# FM_SCH.net
KiCad netlist of a schematic drawn in Altium Designer
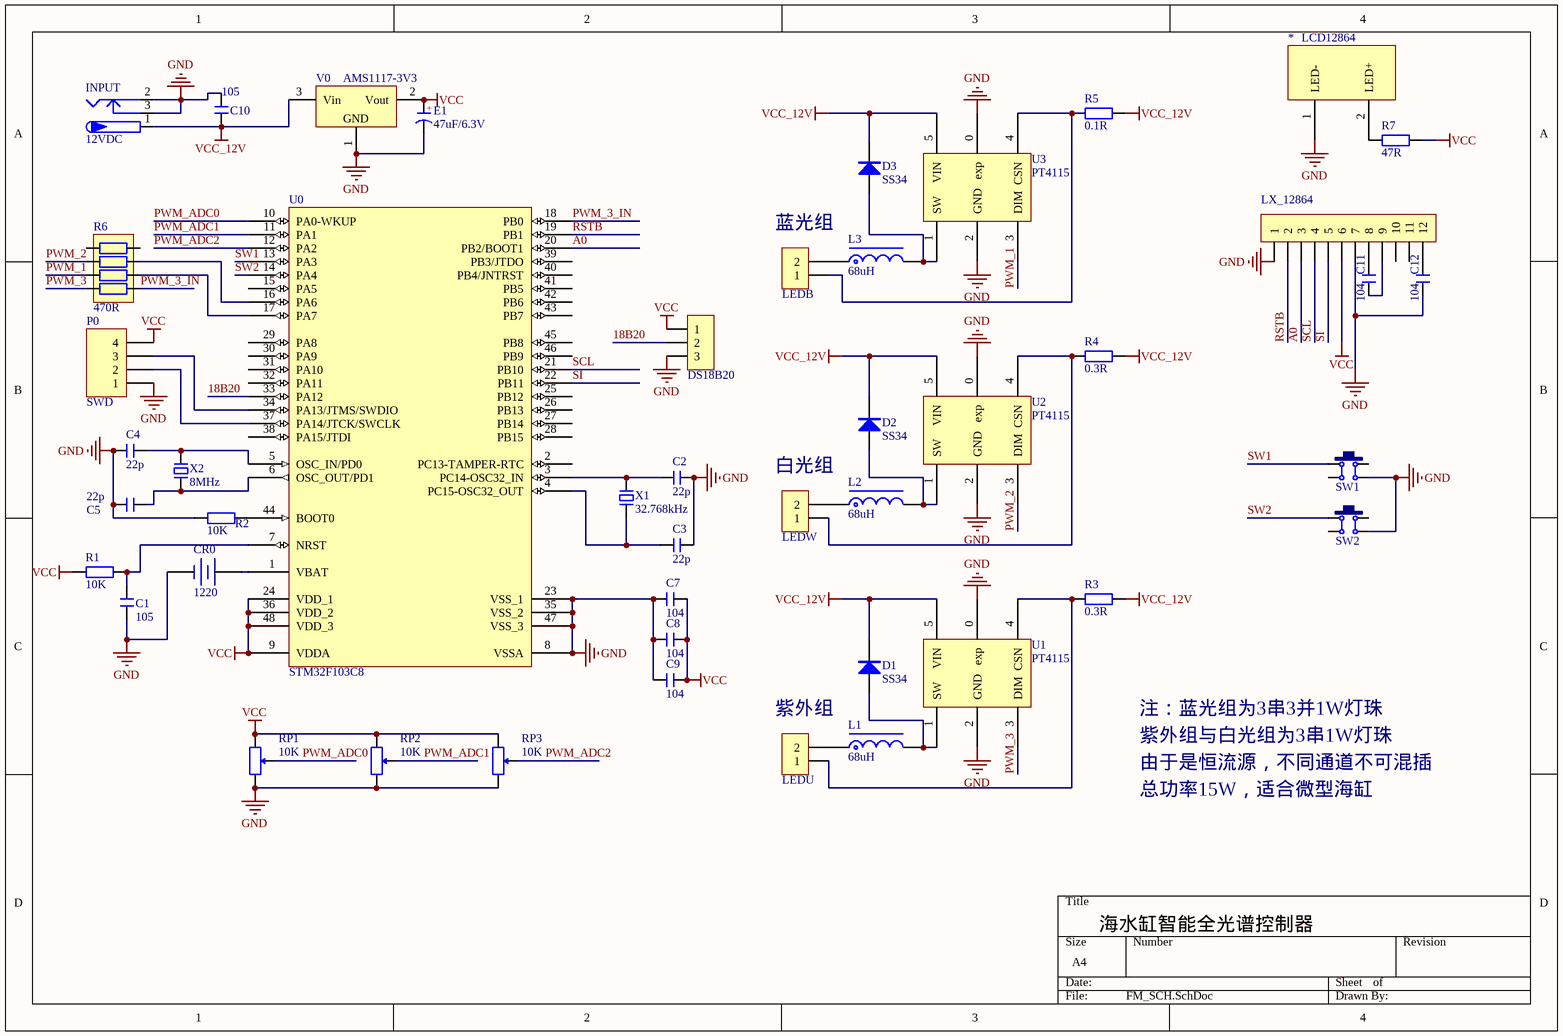
[diagram p0: FM_SCH.SchDoc]

(export (version "E")
  (design (tool "Eeschema 10.0.6"))
  (components
    (comp (ref "*") (value "LCD12864") (footprint "LX_12864") (libsource (lib "F_M_lib") (part "LCD12864")))
    (comp (ref "C1")
      (value "105")
      (footprint "C 0603_L")
      (description "无极性贴片电容")
      (fields (field (name "版权归属") "源创客"))
      (libsource (lib "3.1   - 电阻-电容-电感") (part "C"))
    )
    (comp (ref "C2")
      (value "22p")
      (footprint "C 0603_L")
      (description "无极性贴片电容")
      (fields (field (name "版权归属") "源创客"))
      (libsource (lib "3.1   - 电阻-电容-电感") (part "C"))
    )
    (comp (ref "C3")
      (value "22p")
      (footprint "C 0603_L")
      (description "无极性贴片电容")
      (fields (field (name "版权归属") "源创客"))
      (libsource (lib "3.1   - 电阻-电容-电感") (part "C"))
    )
    (comp (ref "C4")
      (value "22p")
      (footprint "C 0603_L")
      (description "无极性贴片电容")
      (fields (field (name "版权归属") "源创客"))
      (libsource (lib "3.1   - 电阻-电容-电感") (part "C"))
    )
    (comp (ref "C5")
      (value "22p")
      (footprint "C 0603_L")
      (description "无极性贴片电容")
      (fields (field (name "版权归属") "源创客"))
      (libsource (lib "3.1   - 电阻-电容-电感") (part "C"))
    )
    (comp (ref "C7")
      (value "104")
      (footprint "C 0603_L")
      (description "无极性贴片电容")
      (fields (field (name "版权归属") "源创客"))
      (libsource (lib "3.1   - 电阻-电容-电感") (part "C"))
    )
    (comp (ref "C8")
      (value "104")
      (footprint "C 0603_L")
      (description "无极性贴片电容")
      (fields (field (name "版权归属") "源创客"))
      (libsource (lib "3.1   - 电阻-电容-电感") (part "C"))
    )
    (comp (ref "C9")
      (value "104")
      (footprint "C 0603_L")
      (description "无极性贴片电容")
      (fields (field (name "版权归属") "源创客"))
      (libsource (lib "3.1   - 电阻-电容-电感") (part "C"))
    )
    (comp (ref "C10")
      (value "105")
      (footprint "C 0603_L")
      (description "无极性贴片电容")
      (fields (field (name "版权归属") "源创客"))
      (libsource (lib "3.1   - 电阻-电容-电感") (part "C"))
    )
    (comp (ref "C11")
      (value "104")
      (footprint "C 0603_L")
      (description "无极性贴片电容")
      (fields (field (name "版权归属") "源创客"))
      (libsource (lib "3.1   - 电阻-电容-电感") (part "C"))
    )
    (comp (ref "C12")
      (value "104")
      (footprint "C 0603_L")
      (description "无极性贴片电容")
      (fields (field (name "版权归属") "源创客"))
      (libsource (lib "3.1   - 电阻-电容-电感") (part "C"))
    )
    (comp (ref "CR0")
      (value "1220")
      (footprint "CR2032_B")
      (description "微型电池")
      (fields (field (name "版权归属") "源创客"))
      (libsource (lib "15.1 - 未分类器件") (part "CR-3V"))
    )
    (comp (ref "D1")
      (value "SS34")
      (footprint "SMA")
      (description "肖特基二极管")
      (fields (field (name "版权归属") "源创客"))
      (libsource (lib "8.1   - 二极管-整流桥") (part "SS14"))
    )
    (comp (ref "D2")
      (value "SS34")
      (footprint "SMA")
      (description "肖特基二极管")
      (fields (field (name "版权归属") "源创客"))
      (libsource (lib "8.1   - 二极管-整流桥") (part "SS14"))
    )
    (comp (ref "D3")
      (value "SS34")
      (footprint "SMA")
      (description "肖特基二极管")
      (fields (field (name "版权归属") "源创客"))
      (libsource (lib "8.1   - 二极管-整流桥") (part "SS14"))
    )
    (comp (ref "DS18B20")
      (value "HDR-1X3")
      (footprint "XH2.54-WS-3P")
      (description "3P接插件")
      (fields (field (name "版权归属") "源创客"))
      (libsource (lib "4.5   - 接插件-脚距2.54") (part "Header 3"))
    )
    (comp (ref "E1")
      (value "47uF/6.3V")
      (footprint "CD A(3216)")
      (description "贴片钽电容")
      (fields (field (name "版权归属") "源创客"))
      (libsource (lib "3.1   - 电阻-电容-电感") (part "C-CD"))
    )
    (comp (ref "INPUT")
      (value "12VDC")
      (footprint "DC-005")
      (description "低压电源接口")
      (fields (field (name "版权归属") "源创客"))
      (libsource (lib "4.1   - 接口类") (part "P-DC"))
    )
    (comp (ref "L1")
      (value "68uH")
      (footprint "NR5040")
      (description "NR磁胶电感")
      (fields (field (name "版权归属") "源创客"))
      (libsource (lib "3.1   - 电阻-电容-电感") (part "L-NR"))
    )
    (comp (ref "L2")
      (value "68uH")
      (footprint "NR5040")
      (description "NR磁胶电感")
      (fields (field (name "版权归属") "源创客"))
      (libsource (lib "3.1   - 电阻-电容-电感") (part "L-NR"))
    )
    (comp (ref "L3")
      (value "68uH")
      (footprint "NR5040")
      (description "NR磁胶电感")
      (fields (field (name "版权归属") "源创客"))
      (libsource (lib "3.1   - 电阻-电容-电感") (part "L-NR"))
    )
    (comp (ref "LEDB")
      (value "HDR-1X2")
      (footprint "KF2EDGK5.08-WI-2P")
      (description "2P接插件")
      (fields (field (name "版权归属") "源创客"))
      (libsource (lib "4.10 - 接插件-脚距5.08") (part "Header 2"))
    )
    (comp (ref "LEDU")
      (value "HDR-1X2")
      (footprint "KF2EDGK5.08-WI-2P")
      (description "2P接插件")
      (fields (field (name "版权归属") "源创客"))
      (libsource (lib "4.10 - 接插件-脚距5.08") (part "Header 2"))
    )
    (comp (ref "LEDW")
      (value "HDR-1X2")
      (footprint "KF2EDGK5.08-WI-2P")
      (description "2P接插件")
      (fields (field (name "版权归属") "源创客"))
      (libsource (lib "4.10 - 接插件-脚距5.08") (part "Header 2"))
    )
    (comp (ref "LX_12864")
      (value "FPC1.0-12P")
      (footprint "FPC0.5 2H-WS-12P")
      (description "FPC连接器")
      (fields (field (name "版权归属") "源创客"))
      (libsource (lib "4.14 - FPC连接器") (part "FPC-12P"))
    )
    (comp (ref "P0")
      (value "SWD")
      (footprint "HDR1X4")
      (description "Header, 4-Pin")
      (fields (field (name "PUBLISHER") "Altium Limited"))
      (libsource (lib "Miscellaneous Connectors") (part "Header 4"))
    )
    (comp (ref "R1")
      (value "10K")
      (footprint "R 0603_L")
      (description "贴片电阻")
      (fields (field (name "版权归属") "源创客"))
      (libsource (lib "3.1   - 电阻-电容-电感") (part "R"))
    )
    (comp (ref "R2")
      (value "10K")
      (footprint "R 0603_L")
      (description "贴片电阻")
      (fields (field (name "版权归属") "源创客"))
      (libsource (lib "3.1   - 电阻-电容-电感") (part "R"))
    )
    (comp (ref "R3")
      (value "0.3R")
      (footprint "R 2010_L")
      (description "贴片电阻")
      (fields (field (name "版权归属") "源创客"))
      (libsource (lib "3.1   - 电阻-电容-电感") (part "R"))
    )
    (comp (ref "R4")
      (value "0.3R")
      (footprint "R 2010_L")
      (description "贴片电阻")
      (fields (field (name "版权归属") "源创客"))
      (libsource (lib "3.1   - 电阻-电容-电感") (part "R"))
    )
    (comp (ref "R5")
      (value "0.1R")
      (footprint "R 2010_L")
      (description "贴片电阻")
      (fields (field (name "版权归属") "源创客"))
      (libsource (lib "3.1   - 电阻-电容-电感") (part "R"))
    )
    (comp (ref "R6")
      (value "470R")
      (footprint "RCA-8P4R-0603")
      (description "贴片网络排阻")
      (fields (field (name "版权归属") "源创客"))
      (libsource (lib "3.1   - 电阻-电容-电感") (part "R-8P4R"))
    )
    (comp (ref "R7")
      (value "47R")
      (footprint "R 0603_L")
      (description "贴片电阻")
      (fields (field (name "版权归属") "源创客"))
      (libsource (lib "3.1   - 电阻-电容-电感") (part "R"))
    )
    (comp (ref "RP1")
      (value "10K")
      (footprint "WH148-1-G15")
      (description "插件单联电位器")
      (fields (field (name "版权归属") "源创客"))
      (libsource (lib "3.1   - 电阻-电容-电感") (part "RP-ID"))
    )
    (comp (ref "RP2")
      (value "10K")
      (footprint "WH148-1-G15")
      (description "插件单联电位器")
      (fields (field (name "版权归属") "源创客"))
      (libsource (lib "3.1   - 电阻-电容-电感") (part "RP-ID"))
    )
    (comp (ref "RP3")
      (value "10K")
      (footprint "WH148-1-G15")
      (description "插件单联电位器")
      (fields (field (name "版权归属") "源创客"))
      (libsource (lib "3.1   - 电阻-电容-电感") (part "RP-ID"))
    )
    (comp (ref "SW1")
      (value "6x6x5")
      (footprint "TSW DIP-6*6*8")
      (description "直插6x6轻触开关")
      (fields (field (name "版权归属") "源创客"))
      (libsource (lib "5.1   - 按键-开关") (part "TSW DIP-6x6"))
    )
    (comp (ref "SW2")
      (value "6x6x5")
      (footprint "TSW DIP-6*6*8")
      (description "直插6x6轻触开关")
      (fields (field (name "版权归属") "源创客"))
      (libsource (lib "5.1   - 按键-开关") (part "TSW DIP-6x6"))
    )
    (comp (ref "U0")
      (value "STM32F103C8")
      (footprint "LQFP48 7X7_M")
      (description "Flaah:64/RAM:20/IO:36")
      (fields (field (name "版权归属") "源创客"))
      (libsource (lib "2.1   - STM32系列单片机") (part "STM32F103C8"))
    )
    (comp (ref "U1") (value "PT4115") (footprint "SOT89-5") (libsource (lib "F_M_lib") (part "PT4115")))
    (comp (ref "U2") (value "PT4115") (footprint "SOT89-5") (libsource (lib "F_M_lib") (part "PT4115")))
    (comp (ref "U3") (value "PT4115") (footprint "SOT89-5") (libsource (lib "F_M_lib") (part "PT4115")))
    (comp (ref "V0")
      (value "AMS1117-3V3")
      (footprint "SOT223_L")
      (description "三端稳压芯片")
      (fields (field (name "版权归属") "源创客"))
      (libsource (lib "1.3   - 电源类芯片") (part "AMS1117"))
    )
    (comp (ref "X1")
      (value "32.768kHz")
      (footprint "OSC 3215-2P")
      (description "2脚无源脚晶振")
      (fields (field (name "版权归属") "源创客"))
      (libsource (lib "10.1 - 保险丝-晶振") (part "XTAL-2P"))
    )
    (comp (ref "X2")
      (value "8MHz")
      (footprint "OSC HC-49SMD")
      (description "2脚无源脚晶振")
      (fields (field (name "版权归属") "源创客"))
      (libsource (lib "10.1 - 保险丝-晶振") (part "XTAL-2P"))
    )
  )
  (nets
    (net (code "1") (name "/18B20") (class "Default")
      (node (ref "DS18B20") (pin "2") (pinfunction "2_2") (pintype "passive"))
      (node (ref "U0") (pin "33") (pinfunction "PA12_33") (pintype "bidirectional"))
    )
    (net (code "2") (name "/A0") (class "Default")
      (node (ref "LX_12864") (pin "3") (pinfunction "3_3") (pintype "passive"))
      (node (ref "U0") (pin "20") (pinfunction "PB2/BOOT1_20") (pintype "bidirectional"))
    )
    (net (code "3") (name "/PWM_1") (class "Default")
      (node (ref "R6") (pin "3") (pinfunction "3_3") (pintype "passive"))
      (node (ref "U3") (pin "3") (pinfunction "DIM_3") (pintype "passive"))
    )
    (net (code "4") (name "/PWM_2") (class "Default")
      (node (ref "R6") (pin "2") (pinfunction "2_2") (pintype "passive"))
      (node (ref "U2") (pin "3") (pinfunction "DIM_3") (pintype "passive"))
    )
    (net (code "5") (name "/PWM_3") (class "Default")
      (node (ref "R6") (pin "4") (pinfunction "4_4") (pintype "passive"))
      (node (ref "U1") (pin "3") (pinfunction "DIM_3") (pintype "passive"))
    )
    (net (code "6") (name "/PWM_3_IN") (class "Default")
      (node (ref "R6") (pin "5") (pinfunction "5_5") (pintype "passive"))
      (node (ref "U0") (pin "18") (pinfunction "PB0_18") (pintype "bidirectional"))
    )
    (net (code "7") (name "/PWM_ADC0") (class "Default")
      (node (ref "RP1") (pin "2") (pinfunction "2_2") (pintype "passive"))
      (node (ref "U0") (pin "10") (pinfunction "PA0-WKUP_10") (pintype "bidirectional"))
    )
    (net (code "8") (name "/PWM_ADC1") (class "Default")
      (node (ref "RP2") (pin "2") (pinfunction "2_2") (pintype "passive"))
      (node (ref "U0") (pin "11") (pinfunction "PA1_11") (pintype "bidirectional"))
    )
    (net (code "9") (name "/PWM_ADC2") (class "Default")
      (node (ref "RP3") (pin "2") (pinfunction "2_2") (pintype "passive"))
      (node (ref "U0") (pin "12") (pinfunction "PA2_12") (pintype "bidirectional"))
    )
    (net (code "10") (name "/RSTB") (class "Default")
      (node (ref "LX_12864") (pin "2") (pinfunction "2_2") (pintype "passive"))
      (node (ref "U0") (pin "19") (pinfunction "PB1_19") (pintype "bidirectional"))
    )
    (net (code "11") (name "/SCL") (class "Default")
      (node (ref "LX_12864") (pin "4") (pinfunction "4_4") (pintype "passive"))
      (node (ref "U0") (pin "21") (pinfunction "PB10_21") (pintype "bidirectional"))
    )
    (net (code "12") (name "/SI") (class "Default")
      (node (ref "LX_12864") (pin "5") (pinfunction "5_5") (pintype "passive"))
      (node (ref "U0") (pin "22") (pinfunction "PB11_22") (pintype "bidirectional"))
    )
    (net (code "13") (name "/SW1") (class "Default")
      (node (ref "SW1") (pin "1") (pinfunction "1_1") (pintype "passive"))
      (node (ref "U0") (pin "13") (pinfunction "PA3_13") (pintype "bidirectional"))
    )
    (net (code "14") (name "/SW2") (class "Default")
      (node (ref "SW2") (pin "1") (pinfunction "1_1") (pintype "passive"))
      (node (ref "U0") (pin "14") (pinfunction "PA4_14") (pintype "bidirectional"))
    )
    (net (code "15") (name "GND") (class "Default")
      (node (ref "*") (pin "1") (pinfunction "LED-_1") (pintype "passive"))
      (node (ref "C1") (pin "1") (pinfunction "1_1") (pintype "passive"))
      (node (ref "C10") (pin "2") (pinfunction "2_2") (pintype "passive"))
      (node (ref "C12") (pin "2") (pinfunction "2_2") (pintype "passive"))
      (node (ref "C2") (pin "2") (pinfunction "2_2") (pintype "passive"))
      (node (ref "C3") (pin "2") (pinfunction "2_2") (pintype "passive"))
      (node (ref "C4") (pin "1") (pinfunction "1_1") (pintype "passive"))
      (node (ref "C5") (pin "1") (pinfunction "1_1") (pintype "passive"))
      (node (ref "C7") (pin "1") (pinfunction "1_1") (pintype "passive"))
      (node (ref "C8") (pin "1") (pinfunction "1_1") (pintype "passive"))
      (node (ref "C9") (pin "1") (pinfunction "1_1") (pintype "passive"))
      (node (ref "CR0") (pin "2") (pinfunction "DC-_2") (pintype "passive"))
      (node (ref "DS18B20") (pin "3") (pinfunction "3_3") (pintype "passive"))
      (node (ref "E1") (pin "2") (pinfunction "K_2") (pintype "passive"))
      (node (ref "INPUT") (pin "2") (pintype "power_in"))
      (node (ref "INPUT") (pin "3") (pintype "power_in"))
      (node (ref "LX_12864") (pin "1") (pinfunction "1_1") (pintype "passive"))
      (node (ref "LX_12864") (pin "7") (pinfunction "7_7") (pintype "passive"))
      (node (ref "P0") (pin "1") (pinfunction "1_1") (pintype "passive"))
      (node (ref "R2") (pin "1") (pinfunction "1_1") (pintype "passive"))
      (node (ref "RP1") (pin "3") (pinfunction "3_3") (pintype "passive"))
      (node (ref "RP2") (pin "3") (pinfunction "3_3") (pintype "passive"))
      (node (ref "RP3") (pin "3") (pinfunction "3_3") (pintype "passive"))
      (node (ref "SW1") (pin "3") (pinfunction "3_3") (pintype "passive"))
      (node (ref "SW2") (pin "3") (pinfunction "3_3") (pintype "passive"))
      (node (ref "U0") (pin "23") (pinfunction "VSS_1_23") (pintype "power_in"))
      (node (ref "U0") (pin "35") (pinfunction "VSS_2_35") (pintype "power_in"))
      (node (ref "U0") (pin "47") (pinfunction "VSS_3_47") (pintype "power_in"))
      (node (ref "U0") (pin "8") (pinfunction "VSSA_8") (pintype "power_in"))
      (node (ref "U1") (pin "0") (pinfunction "exp_0") (pintype "passive"))
      (node (ref "U1") (pin "2") (pinfunction "GND_2") (pintype "passive"))
      (node (ref "U2") (pin "0") (pinfunction "exp_0") (pintype "passive"))
      (node (ref "U2") (pin "2") (pinfunction "GND_2") (pintype "passive"))
      (node (ref "U3") (pin "0") (pinfunction "exp_0") (pintype "passive"))
      (node (ref "U3") (pin "2") (pinfunction "GND_2") (pintype "passive"))
      (node (ref "V0") (pin "1") (pinfunction "GND_1") (pintype "passive"))
    )
    (net (code "16") (name "Net-(*-LED+)") (class "Default")
      (node (ref "*") (pin "2") (pinfunction "LED+_2") (pintype "passive"))
      (node (ref "R7") (pin "1") (pinfunction "1_1") (pintype "passive"))
    )
    (net (code "17") (name "Net-(C11-Pad1)") (class "Default")
      (node (ref "C11") (pin "1") (pinfunction "1_1") (pintype "passive"))
      (node (ref "LX_12864") (pin "9") (pinfunction "9_9") (pintype "passive"))
    )
    (net (code "18") (name "Net-(C11-Pad2)") (class "Default")
      (node (ref "C11") (pin "2") (pinfunction "2_2") (pintype "passive"))
      (node (ref "LX_12864") (pin "8") (pinfunction "8_8") (pintype "passive"))
    )
    (net (code "19") (name "Net-(C12-Pad1)") (class "Default")
      (node (ref "C12") (pin "1") (pinfunction "1_1") (pintype "passive"))
      (node (ref "LX_12864") (pin "12") (pinfunction "12_12") (pintype "passive"))
    )
    (net (code "20") (name "Net-(CR0-DC+)") (class "Default")
      (node (ref "CR0") (pin "1") (pinfunction "DC+_1") (pintype "passive"))
      (node (ref "U0") (pin "1") (pinfunction "VBAT_1") (pintype "power_in"))
    )
    (net (code "21") (name "Net-(D1-A)") (class "Default")
      (node (ref "D1") (pin "1") (pinfunction "A_1") (pintype "passive"))
      (node (ref "L1") (pin "2") (pinfunction "2_2") (pintype "passive"))
      (node (ref "U1") (pin "1") (pinfunction "SW_1") (pintype "passive"))
    )
    (net (code "22") (name "Net-(D2-A)") (class "Default")
      (node (ref "D2") (pin "1") (pinfunction "A_1") (pintype "passive"))
      (node (ref "L2") (pin "2") (pinfunction "2_2") (pintype "passive"))
      (node (ref "U2") (pin "1") (pinfunction "SW_1") (pintype "passive"))
    )
    (net (code "23") (name "Net-(D3-A)") (class "Default")
      (node (ref "D3") (pin "1") (pinfunction "A_1") (pintype "passive"))
      (node (ref "L3") (pin "2") (pinfunction "2_2") (pintype "passive"))
      (node (ref "U3") (pin "1") (pinfunction "SW_1") (pintype "passive"))
    )
    (net (code "24") (name "Net-(L1-Pad1)") (class "Default")
      (node (ref "L1") (pin "1") (pinfunction "1_1") (pintype "passive"))
      (node (ref "LEDU") (pin "2") (pinfunction "2_2") (pintype "passive"))
    )
    (net (code "25") (name "Net-(L2-Pad1)") (class "Default")
      (node (ref "L2") (pin "1") (pinfunction "1_1") (pintype "passive"))
      (node (ref "LEDW") (pin "2") (pinfunction "2_2") (pintype "passive"))
    )
    (net (code "26") (name "Net-(L3-Pad1)") (class "Default")
      (node (ref "L3") (pin "1") (pinfunction "1_1") (pintype "passive"))
      (node (ref "LEDB") (pin "2") (pinfunction "2_2") (pintype "passive"))
    )
    (net (code "27") (name "Net-(U0-BOOT0)") (class "Default")
      (node (ref "R2") (pin "2") (pinfunction "2_2") (pintype "passive"))
      (node (ref "U0") (pin "44") (pinfunction "BOOT0_44") (pintype "input"))
    )
    (net (code "28") (name "Net-(U0-NRST)") (class "Default")
      (node (ref "C1") (pin "2") (pinfunction "2_2") (pintype "passive"))
      (node (ref "R1") (pin "2") (pinfunction "2_2") (pintype "passive"))
      (node (ref "U0") (pin "7") (pinfunction "NRST_7") (pintype "bidirectional"))
    )
    (net (code "29") (name "Net-(U0-OSC_IN{slash}PD0)") (class "Default")
      (node (ref "C4") (pin "2") (pinfunction "2_2") (pintype "passive"))
      (node (ref "U0") (pin "5") (pinfunction "OSC_IN/PD0_5") (pintype "input"))
      (node (ref "X2") (pin "2") (pinfunction "2_2") (pintype "passive"))
    )
    (net (code "30") (name "Net-(U0-OSC_OUT{slash}PD1)") (class "Default")
      (node (ref "C5") (pin "2") (pinfunction "2_2") (pintype "passive"))
      (node (ref "U0") (pin "6") (pinfunction "OSC_OUT/PD1_6") (pintype "output"))
      (node (ref "X2") (pin "1") (pinfunction "1_1") (pintype "passive"))
    )
    (net (code "31") (name "Net-(U0-PA6)") (class "Default")
      (node (ref "R6") (pin "7") (pinfunction "7_7") (pintype "passive"))
      (node (ref "U0") (pin "16") (pinfunction "PA6_16") (pintype "bidirectional"))
    )
    (net (code "32") (name "Net-(U0-PA7)") (class "Default")
      (node (ref "R6") (pin "6") (pinfunction "6_6") (pintype "passive"))
      (node (ref "U0") (pin "17") (pinfunction "PA7_17") (pintype "bidirectional"))
    )
    (net (code "33") (name "Net-(U0-PA13{slash}JTMS{slash}SWDIO)") (class "Default")
      (node (ref "P0") (pin "3") (pinfunction "3_3") (pintype "passive"))
      (node (ref "U0") (pin "34") (pinfunction "PA13/JTMS/SWDIO_34") (pintype "bidirectional"))
    )
    (net (code "34") (name "Net-(U0-PA14{slash}JTCK{slash}SWCLK)") (class "Default")
      (node (ref "P0") (pin "2") (pinfunction "2_2") (pintype "passive"))
      (node (ref "U0") (pin "37") (pinfunction "PA14/JTCK/SWCLK_37") (pintype "bidirectional"))
    )
    (net (code "35") (name "Net-(U0-PC14-OSC32_IN)") (class "Default")
      (node (ref "C2") (pin "1") (pinfunction "1_1") (pintype "passive"))
      (node (ref "U0") (pin "3") (pinfunction "PC14-OSC32_IN_3") (pintype "bidirectional"))
      (node (ref "X1") (pin "2") (pinfunction "2_2") (pintype "passive"))
    )
    (net (code "36") (name "Net-(U0-PC15-OSC32_OUT)") (class "Default")
      (node (ref "C3") (pin "1") (pinfunction "1_1") (pintype "passive"))
      (node (ref "U0") (pin "4") (pinfunction "PC15-OSC32_OUT_4") (pintype "bidirectional"))
      (node (ref "X1") (pin "1") (pinfunction "1_1") (pintype "passive"))
    )
    (net (code "37") (name "Net-(U1-CSN)") (class "Default")
      (node (ref "LEDU") (pin "1") (pinfunction "1_1") (pintype "passive"))
      (node (ref "R3") (pin "1") (pinfunction "1_1") (pintype "passive"))
      (node (ref "U1") (pin "4") (pinfunction "CSN_4") (pintype "passive"))
    )
    (net (code "38") (name "Net-(U2-CSN)") (class "Default")
      (node (ref "LEDW") (pin "1") (pinfunction "1_1") (pintype "passive"))
      (node (ref "R4") (pin "1") (pinfunction "1_1") (pintype "passive"))
      (node (ref "U2") (pin "4") (pinfunction "CSN_4") (pintype "passive"))
    )
    (net (code "39") (name "Net-(U3-CSN)") (class "Default")
      (node (ref "LEDB") (pin "1") (pinfunction "1_1") (pintype "passive"))
      (node (ref "R5") (pin "1") (pinfunction "1_1") (pintype "passive"))
      (node (ref "U3") (pin "4") (pinfunction "CSN_4") (pintype "passive"))
    )
    (net (code "40") (name "VCC") (class "Default")
      (node (ref "C7") (pin "2") (pinfunction "2_2") (pintype "passive"))
      (node (ref "C8") (pin "2") (pinfunction "2_2") (pintype "passive"))
      (node (ref "C9") (pin "2") (pinfunction "2_2") (pintype "passive"))
      (node (ref "DS18B20") (pin "1") (pinfunction "1_1") (pintype "passive"))
      (node (ref "E1") (pin "1") (pinfunction "A_1") (pintype "passive"))
      (node (ref "LX_12864") (pin "6") (pinfunction "6_6") (pintype "passive"))
      (node (ref "P0") (pin "4") (pinfunction "4_4") (pintype "passive"))
      (node (ref "R1") (pin "1") (pinfunction "1_1") (pintype "passive"))
      (node (ref "R7") (pin "2") (pinfunction "2_2") (pintype "passive"))
      (node (ref "RP1") (pin "1") (pinfunction "1_1") (pintype "passive"))
      (node (ref "RP2") (pin "1") (pinfunction "1_1") (pintype "passive"))
      (node (ref "RP3") (pin "1") (pinfunction "1_1") (pintype "passive"))
      (node (ref "U0") (pin "24") (pinfunction "VDD_1_24") (pintype "power_in"))
      (node (ref "U0") (pin "36") (pinfunction "VDD_2_36") (pintype "power_in"))
      (node (ref "U0") (pin "48") (pinfunction "VDD_3_48") (pintype "power_in"))
      (node (ref "U0") (pin "9") (pinfunction "VDDA_9") (pintype "power_in"))
      (node (ref "V0") (pin "2") (pinfunction "Vout_2") (pintype "passive"))
    )
    (net (code "41") (name "VCC_12V") (class "Default")
      (node (ref "C10") (pin "1") (pinfunction "1_1") (pintype "passive"))
      (node (ref "D1") (pin "2") (pinfunction "K_2") (pintype "passive"))
      (node (ref "D2") (pin "2") (pinfunction "K_2") (pintype "passive"))
      (node (ref "D3") (pin "2") (pinfunction "K_2") (pintype "passive"))
      (node (ref "INPUT") (pin "1") (pintype "power_in"))
      (node (ref "R3") (pin "2") (pinfunction "2_2") (pintype "passive"))
      (node (ref "R4") (pin "2") (pinfunction "2_2") (pintype "passive"))
      (node (ref "R5") (pin "2") (pinfunction "2_2") (pintype "passive"))
      (node (ref "U1") (pin "5") (pinfunction "VIN_5") (pintype "passive"))
      (node (ref "U2") (pin "5") (pinfunction "VIN_5") (pintype "passive"))
      (node (ref "U3") (pin "5") (pinfunction "VIN_5") (pintype "passive"))
      (node (ref "V0") (pin "3") (pinfunction "Vin_3") (pintype "passive"))
    )
    (net (code "42") (name "unconnected-(LX_12864-Pad10)") (class "Default")
      (node (ref "LX_12864") (pin "10") (pinfunction "10_10") (pintype "passive"))
    )
    (net (code "43") (name "unconnected-(LX_12864-Pad11)") (class "Default")
      (node (ref "LX_12864") (pin "11") (pinfunction "11_11") (pintype "passive"))
    )
    (net (code "44") (name "unconnected-(R6-Pad1)") (class "Default")
      (node (ref "R6") (pin "1") (pinfunction "1_1") (pintype "passive"))
    )
    (net (code "45") (name "unconnected-(R6-Pad8)") (class "Default")
      (node (ref "R6") (pin "8") (pinfunction "8_8") (pintype "passive"))
    )
    (net (code "46") (name "unconnected-(SW1-Pad2)") (class "Default")
      (node (ref "SW1") (pin "2") (pinfunction "2_2") (pintype "passive"))
    )
    (net (code "47") (name "unconnected-(SW1-Pad4)") (class "Default")
      (node (ref "SW1") (pin "4") (pinfunction "4_4") (pintype "passive"))
    )
    (net (code "48") (name "unconnected-(SW2-Pad2)") (class "Default")
      (node (ref "SW2") (pin "2") (pinfunction "2_2") (pintype "passive"))
    )
    (net (code "49") (name "unconnected-(SW2-Pad4)") (class "Default")
      (node (ref "SW2") (pin "4") (pinfunction "4_4") (pintype "passive"))
    )
    (net (code "50") (name "unconnected-(U0-PA5-Pad15)") (class "Default")
      (node (ref "U0") (pin "15") (pinfunction "PA5_15") (pintype "bidirectional"))
    )
    (net (code "51") (name "unconnected-(U0-PA8-Pad29)") (class "Default")
      (node (ref "U0") (pin "29") (pinfunction "PA8_29") (pintype "bidirectional"))
    )
    (net (code "52") (name "unconnected-(U0-PA9-Pad30)") (class "Default")
      (node (ref "U0") (pin "30") (pinfunction "PA9_30") (pintype "bidirectional"))
    )
    (net (code "53") (name "unconnected-(U0-PA10-Pad31)") (class "Default")
      (node (ref "U0") (pin "31") (pinfunction "PA10_31") (pintype "bidirectional"))
    )
    (net (code "54") (name "unconnected-(U0-PA11-Pad32)") (class "Default")
      (node (ref "U0") (pin "32") (pinfunction "PA11_32") (pintype "bidirectional"))
    )
    (net (code "55") (name "unconnected-(U0-PA15{slash}JTDI-Pad38)") (class "Default")
      (node (ref "U0") (pin "38") (pinfunction "PA15/JTDI_38") (pintype "bidirectional"))
    )
    (net (code "56") (name "unconnected-(U0-PB3{slash}JTDO-Pad39)") (class "Default")
      (node (ref "U0") (pin "39") (pinfunction "PB3/JTDO_39") (pintype "bidirectional"))
    )
    (net (code "57") (name "unconnected-(U0-PB4{slash}JNTRST-Pad40)") (class "Default")
      (node (ref "U0") (pin "40") (pinfunction "PB4/JNTRST_40") (pintype "bidirectional"))
    )
    (net (code "58") (name "unconnected-(U0-PB5-Pad41)") (class "Default")
      (node (ref "U0") (pin "41") (pinfunction "PB5_41") (pintype "bidirectional"))
    )
    (net (code "59") (name "unconnected-(U0-PB6-Pad42)") (class "Default")
      (node (ref "U0") (pin "42") (pinfunction "PB6_42") (pintype "bidirectional"))
    )
    (net (code "60") (name "unconnected-(U0-PB7-Pad43)") (class "Default")
      (node (ref "U0") (pin "43") (pinfunction "PB7_43") (pintype "bidirectional"))
    )
    (net (code "61") (name "unconnected-(U0-PB8-Pad45)") (class "Default")
      (node (ref "U0") (pin "45") (pinfunction "PB8_45") (pintype "bidirectional"))
    )
    (net (code "62") (name "unconnected-(U0-PB9-Pad46)") (class "Default")
      (node (ref "U0") (pin "46") (pinfunction "PB9_46") (pintype "bidirectional"))
    )
    (net (code "63") (name "unconnected-(U0-PB12-Pad25)") (class "Default")
      (node (ref "U0") (pin "25") (pinfunction "PB12_25") (pintype "bidirectional"))
    )
    (net (code "64") (name "unconnected-(U0-PB13-Pad26)") (class "Default")
      (node (ref "U0") (pin "26") (pinfunction "PB13_26") (pintype "bidirectional"))
    )
    (net (code "65") (name "unconnected-(U0-PB14-Pad27)") (class "Default")
      (node (ref "U0") (pin "27") (pinfunction "PB14_27") (pintype "bidirectional"))
    )
    (net (code "66") (name "unconnected-(U0-PB15-Pad28)") (class "Default")
      (node (ref "U0") (pin "28") (pinfunction "PB15_28") (pintype "bidirectional"))
    )
    (net (code "67") (name "unconnected-(U0-PC13-TAMPER-RTC-Pad2)") (class "Default")
      (node (ref "U0") (pin "2") (pinfunction "PC13-TAMPER-RTC_2") (pintype "bidirectional"))
    )
  )
)
